# Power.net
KiCad netlist of a schematic drawn in Altium Designer
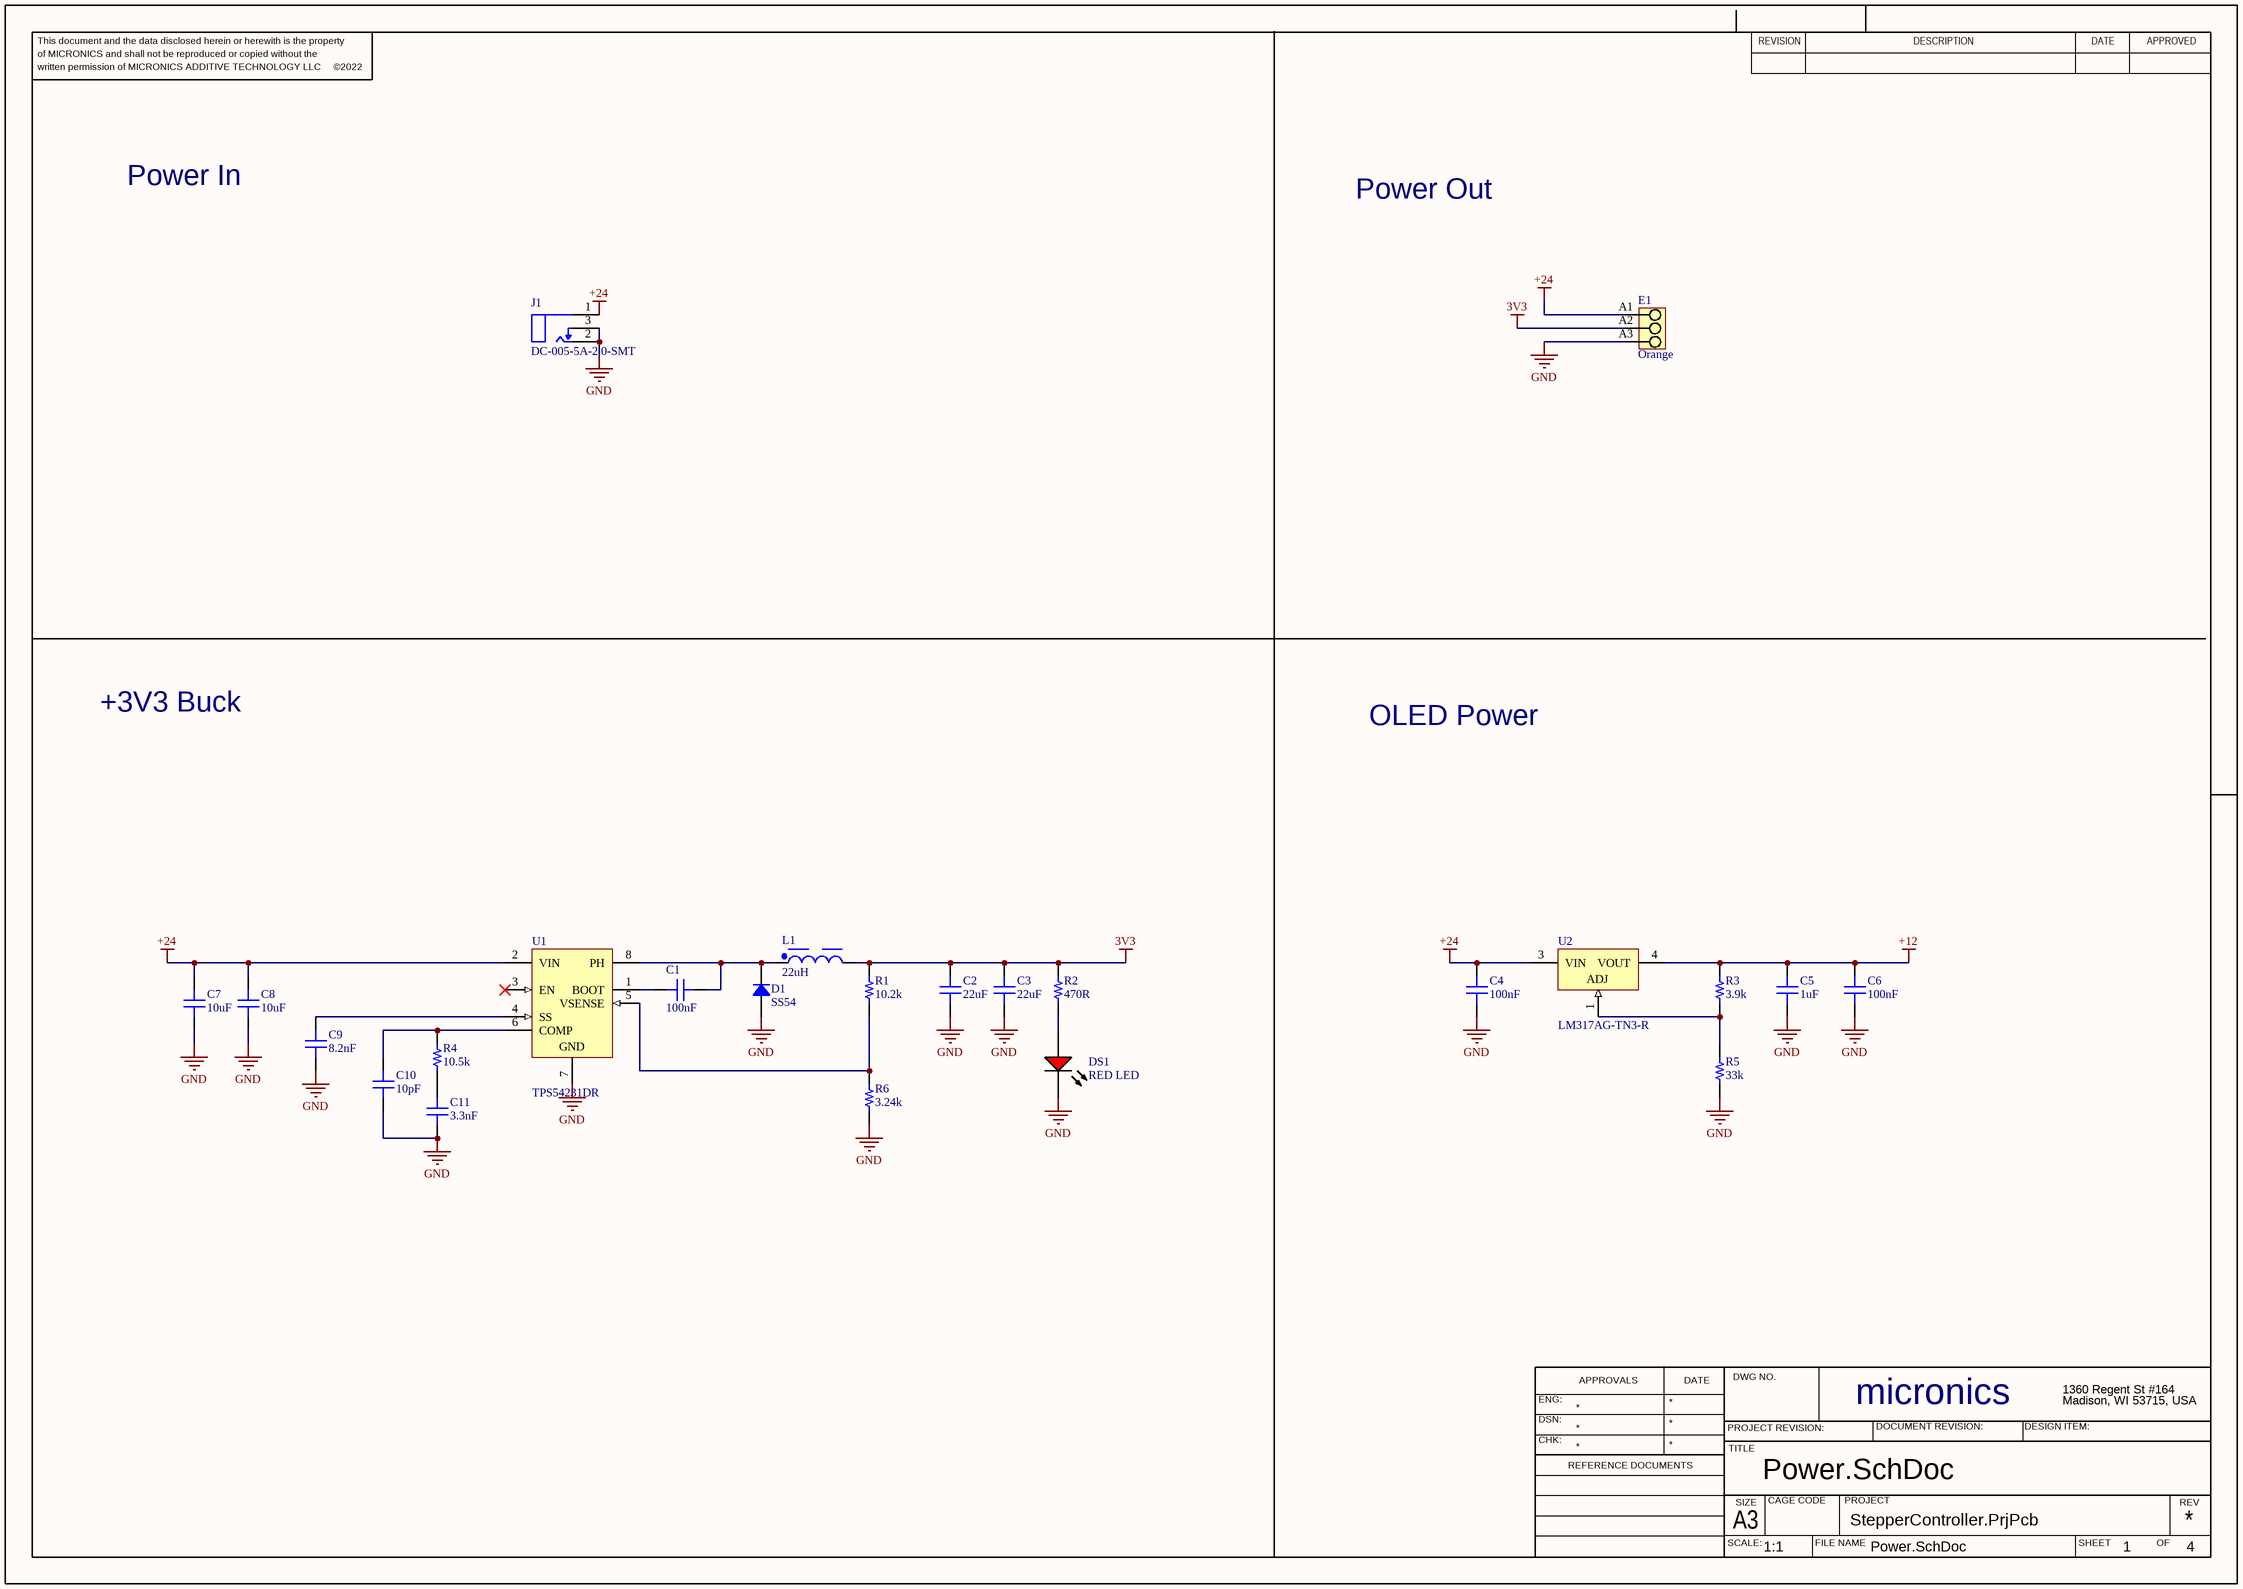
[diagram p0: Power.SchDoc]

(export (version "E")
  (design (tool "Eeschema 10.0.6"))
  (components
    (comp (ref "C1")
      (value "100nF")
      (footprint "CAP 0603_1608")
      (description "C14663")
      (fields
        (field (name "PART NUMBER") "250X14W223MV4T")
        (field (name "MANUFACTURER") "Johanson Dielectrics Inc.")
      )
      (libsource (lib "Celestial Altium Library - altium_library") (part "Capacitor"))
    )
    (comp (ref "C2")
      (value "22uF")
      (footprint "CAP 1206_3216 - 0.8MM")
      (description "C12891")
      (fields (field (name "PART NUMBER") "MM061A101JCT2A") (field (name "MANUFACTURER") "AVX Corporation"))
      (libsource (lib "Celestial Altium Library - altium_library") (part "Capacitor"))
    )
    (comp (ref "C3")
      (value "22uF")
      (footprint "CAP 1206_3216 - 0.8MM")
      (description "C12891")
      (fields (field (name "PART NUMBER") "MM061A101JCT2A") (field (name "MANUFACTURER") "AVX Corporation"))
      (libsource (lib "Celestial Altium Library - altium_library") (part "Capacitor"))
    )
    (comp (ref "C4")
      (value "100nF")
      (footprint "CAP 0603_1608")
      (description "CAP CER 0.022UF 25V X7R 0603")
      (fields
        (field (name "PART NUMBER") "250X14W223MV4T")
        (field (name "MANUFACTURER") "Johanson Dielectrics Inc.")
      )
      (libsource (lib "Celestial Altium Library - altium_library") (part "Capacitor"))
    )
    (comp (ref "C5")
      (value "1uF")
      (footprint "CAP 0603_1608")
      (description "CAP CER 0.022UF 25V X7R 0603")
      (fields
        (field (name "PART NUMBER") "250X14W223MV4T")
        (field (name "MANUFACTURER") "Johanson Dielectrics Inc.")
      )
      (libsource (lib "Celestial Altium Library - altium_library") (part "Capacitor"))
    )
    (comp (ref "C6")
      (value "100nF")
      (footprint "CAP 0603_1608")
      (description "CAP CER 0.022UF 25V X7R 0603")
      (fields
        (field (name "PART NUMBER") "250X14W223MV4T")
        (field (name "MANUFACTURER") "Johanson Dielectrics Inc.")
      )
      (libsource (lib "Celestial Altium Library - altium_library") (part "Capacitor"))
    )
    (comp (ref "C7")
      (value "10uF")
      (footprint "CAP 1206_3216 - 0.8MM")
      (description "C13585")
      (fields (field (name "PART NUMBER") "MM061A101JCT2A") (field (name "MANUFACTURER") "AVX Corporation"))
      (libsource (lib "Celestial Altium Library - altium_library") (part "Capacitor"))
    )
    (comp (ref "C8")
      (value "10uF")
      (footprint "CAP 1206_3216 - 0.8MM")
      (description "C13585")
      (fields (field (name "PART NUMBER") "MM061A101JCT2A") (field (name "MANUFACTURER") "AVX Corporation"))
      (libsource (lib "Celestial Altium Library - altium_library") (part "Capacitor"))
    )
    (comp (ref "C9")
      (value "8.2nF")
      (footprint "CAP 0603_1608")
      (fields
        (field (name "PART NUMBER") "250X14W223MV4T")
        (field (name "MANUFACTURER") "Johanson Dielectrics Inc.")
        (field (name "TOLERANCE") "±20%")
      )
      (libsource (lib "Celestial Altium Library - altium_library") (part "Capacitor"))
    )
    (comp (ref "C10")
      (value "10pF")
      (footprint "CAP 0603_1608")
      (fields
        (field (name "PART NUMBER") "250X14W223MV4T")
        (field (name "MANUFACTURER") "Johanson Dielectrics Inc.")
        (field (name "TOLERANCE") "±20%")
      )
      (libsource (lib "Celestial Altium Library - altium_library") (part "Capacitor"))
    )
    (comp (ref "C11")
      (value "3.3nF")
      (footprint "CAP 0603_1608")
      (fields
        (field (name "PART NUMBER") "250X14W223MV4T")
        (field (name "MANUFACTURER") "Johanson Dielectrics Inc.")
        (field (name "TOLERANCE") "±20%")
      )
      (libsource (lib "Celestial Altium Library - altium_library") (part "Capacitor"))
    )
    (comp (ref "D1")
      (value "SS54")
      (footprint "DO214AC SMA")
      (fields (field (name "MANUFACTURER") "ON Semiconductor"))
      (libsource (lib "Celestial Altium Library - altium_library") (part "Diode"))
    )
    (comp (ref "DS1")
      (value "RED LED")
      (footprint "VISH-TLMS1000_V")
      (description "0603 LED")
      (fields (field (name "MANUFACTURER") "Vishay"))
      (libsource (lib "Altium Content Vault") (part "LED-RED-AK-2"))
    )
    (comp (ref "E1")
      (value "Orange")
      (footprint "PM_5_08_90_03")
      (description "C430604")
      (fields (field (name "PARTNUMBER") "1760500000") (field (name "MANUFACTURER") "Weidmueller"))
      (libsource (lib "Altium Content Vault") (part "Terminal_03_1x03"))
    )
    (comp (ref "J1")
      (value "DC-005-5A-2.0-SMT")
      (footprint "FP-PJ-002BH-SMT-TR-MFG")
      (description "C319134")
      (fields
        (field (name "MANUFACTURER") "CUI Inc")
        (field (name "OCTOPART") "https://octopart.com/pj-002bh-smt-tr-cui-25947151")
      )
      (libsource (lib "Altium Content Vault") (part "020ff674638626da6de6501228ee46e"))
    )
    (comp (ref "L1")
      (value "22uH")
      (footprint "WE-PD_1050P")
      (description "C2651173")
      (fields (field (name "TOLERANCE") "20%"))
      (libsource (lib "Altium Content Vault") (part "Inductor - 2"))
    )
    (comp (ref "R1")
      (value "10.2k")
      (footprint "RES 0603_1608")
      (description "RES 23.2K OHM 0.5% 1/10W 0603")
      (fields
        (field (name "PART NUMBER") "RNCF0603DTE23K2")
        (field (name "MANUFACTURER") "Stackpole Electronics Inc")
      )
      (libsource (lib "Celestial Altium Library - altium_library") (part "Resistor"))
    )
    (comp (ref "R2")
      (value "470R")
      (footprint "RES 0603_1608")
      (description "RES 23.2K OHM 0.5% 1/10W 0603")
      (fields
        (field (name "PART NUMBER") "RNCF0603DTE23K2")
        (field (name "MANUFACTURER") "Stackpole Electronics Inc")
      )
      (libsource (lib "Celestial Altium Library - altium_library") (part "Resistor"))
    )
    (comp (ref "R3")
      (value "3.9k")
      (footprint "RES 0603_1608")
      (description "RES 23.2K OHM 0.5% 1/10W 0603")
      (fields
        (field (name "PART NUMBER") "RNCF0603DTE23K2")
        (field (name "MANUFACTURER") "Stackpole Electronics Inc")
      )
      (libsource (lib "Celestial Altium Library - altium_library") (part "Resistor"))
    )
    (comp (ref "R4")
      (value "10.5k")
      (footprint "RES 0603_1608")
      (description "RES 23.2K OHM 0.5% 1/10W 0603")
      (fields
        (field (name "PART NUMBER") "RNCF0603DTE23K2")
        (field (name "MANUFACTURER") "Stackpole Electronics Inc")
      )
      (libsource (lib "Celestial Altium Library - altium_library") (part "Resistor"))
    )
    (comp (ref "R5")
      (value "33k")
      (footprint "RES 0603_1608")
      (description "RES 23.2K OHM 0.5% 1/10W 0603")
      (fields
        (field (name "PART NUMBER") "RNCF0603DTE23K2")
        (field (name "MANUFACTURER") "Stackpole Electronics Inc")
      )
      (libsource (lib "Celestial Altium Library - altium_library") (part "Resistor"))
    )
    (comp (ref "R6")
      (value "3.24k")
      (footprint "RES 0603_1608")
      (description "RES 23.2K OHM 0.5% 1/10W 0603")
      (fields
        (field (name "PART NUMBER") "RNCF0603DTE23K2")
        (field (name "MANUFACTURER") "Stackpole Electronics Inc")
      )
      (libsource (lib "Celestial Altium Library - altium_library") (part "Resistor"))
    )
    (comp (ref "U1")
      (value "TPS54231DR")
      (footprint "D0008A_L")
      (fields (field (name "MANUFACTURER") "Texas Instruments"))
      (libsource (lib "Altium Content Vault") (part "TI-TPS54231D8"))
    )
    (comp (ref "U2")
      (value "LM317AG-TN3-R")
      (footprint "TO-252_L")
      (description "C75510")
      (libsource (lib "Altium Content Vault") (part "PM-REG-LM217M-SOT3"))
    )
  )
  (nets
    (net (code "1") (name "+12") (class "Default")
      (node (ref "C5") (pin "1") (pinfunction "1_1") (pintype "passive"))
      (node (ref "C6") (pin "1") (pinfunction "1_1") (pintype "passive"))
      (node (ref "R3") (pin "2") (pinfunction "2_2") (pintype "passive"))
      (node (ref "U2") (pin "4") (pinfunction "VOUT_4") (pintype "power_in"))
    )
    (net (code "2") (name "+24") (class "Default")
      (node (ref "C4") (pin "1") (pinfunction "1_1") (pintype "passive"))
      (node (ref "C7") (pin "2") (pinfunction "2_2") (pintype "passive"))
      (node (ref "C8") (pin "2") (pinfunction "2_2") (pintype "passive"))
      (node (ref "E1") (pin "A1") (pinfunction "A1_A1") (pintype "passive"))
      (node (ref "J1") (pin "1") (pinfunction "1_1") (pintype "passive"))
      (node (ref "U1") (pin "2") (pinfunction "VIN_2") (pintype "power_in"))
      (node (ref "U2") (pin "3") (pinfunction "VIN_3") (pintype "power_in"))
    )
    (net (code "3") (name "3V3") (class "Default")
      (node (ref "C2") (pin "2") (pinfunction "2_2") (pintype "passive"))
      (node (ref "C3") (pin "2") (pinfunction "2_2") (pintype "passive"))
      (node (ref "E1") (pin "A2") (pinfunction "A2_A2") (pintype "passive"))
      (node (ref "L1") (pin "2") (pinfunction "2_2") (pintype "passive"))
      (node (ref "R1") (pin "2") (pinfunction "2_2") (pintype "passive"))
      (node (ref "R2") (pin "2") (pinfunction "2_2") (pintype "passive"))
    )
    (net (code "4") (name "GND") (class "Default")
      (node (ref "C10") (pin "1") (pinfunction "1_1") (pintype "passive"))
      (node (ref "C11") (pin "1") (pinfunction "1_1") (pintype "passive"))
      (node (ref "C2") (pin "1") (pinfunction "1_1") (pintype "passive"))
      (node (ref "C3") (pin "1") (pinfunction "1_1") (pintype "passive"))
      (node (ref "C4") (pin "2") (pinfunction "2_2") (pintype "passive"))
      (node (ref "C5") (pin "2") (pinfunction "2_2") (pintype "passive"))
      (node (ref "C6") (pin "2") (pinfunction "2_2") (pintype "passive"))
      (node (ref "C7") (pin "1") (pinfunction "1_1") (pintype "passive"))
      (node (ref "C8") (pin "1") (pinfunction "1_1") (pintype "passive"))
      (node (ref "C9") (pin "1") (pinfunction "1_1") (pintype "passive"))
      (node (ref "D1") (pin "1") (pinfunction "1_1") (pintype "passive"))
      (node (ref "DS1") (pin "2") (pinfunction "K_2") (pintype "passive"))
      (node (ref "E1") (pin "A3") (pinfunction "A3_A3") (pintype "passive"))
      (node (ref "J1") (pin "2") (pinfunction "2_2") (pintype "passive"))
      (node (ref "J1") (pin "3") (pinfunction "3_3") (pintype "passive"))
      (node (ref "R5") (pin "1") (pinfunction "1_1") (pintype "passive"))
      (node (ref "R6") (pin "1") (pinfunction "1_1") (pintype "passive"))
      (node (ref "U1") (pin "7") (pinfunction "GND_7") (pintype "power_in"))
    )
    (net (code "5") (name "Net-(C11-Pad2)") (class "Default")
      (node (ref "C11") (pin "2") (pinfunction "2_2") (pintype "passive"))
      (node (ref "R4") (pin "1") (pinfunction "1_1") (pintype "passive"))
    )
    (net (code "6") (name "Net-(DS1-A)") (class "Default")
      (node (ref "DS1") (pin "1") (pinfunction "A_1") (pintype "passive"))
      (node (ref "R2") (pin "1") (pinfunction "1_1") (pintype "passive"))
    )
    (net (code "7") (name "Net-(U1-BOOT)") (class "Default")
      (node (ref "C1") (pin "2") (pinfunction "2_2") (pintype "passive"))
      (node (ref "U1") (pin "1") (pinfunction "BOOT_1") (pintype "passive"))
    )
    (net (code "8") (name "Net-(U1-COMP)") (class "Default")
      (node (ref "C10") (pin "2") (pinfunction "2_2") (pintype "passive"))
      (node (ref "R4") (pin "2") (pinfunction "2_2") (pintype "passive"))
      (node (ref "U1") (pin "6") (pinfunction "COMP_6") (pintype "passive"))
    )
    (net (code "9") (name "Net-(U1-PH)") (class "Default")
      (node (ref "C1") (pin "1") (pinfunction "1_1") (pintype "passive"))
      (node (ref "D1") (pin "2") (pinfunction "2_2") (pintype "passive"))
      (node (ref "L1") (pin "1") (pinfunction "1_1") (pintype "passive"))
      (node (ref "U1") (pin "8") (pinfunction "PH_8") (pintype "power_in"))
    )
    (net (code "10") (name "Net-(U1-SS)") (class "Default")
      (node (ref "C9") (pin "2") (pinfunction "2_2") (pintype "passive"))
      (node (ref "U1") (pin "4") (pinfunction "SS_4") (pintype "input"))
    )
    (net (code "11") (name "Net-(U1-VSENSE)") (class "Default")
      (node (ref "R1") (pin "1") (pinfunction "1_1") (pintype "passive"))
      (node (ref "R6") (pin "2") (pinfunction "2_2") (pintype "passive"))
      (node (ref "U1") (pin "5") (pinfunction "VSENSE_5") (pintype "input"))
    )
    (net (code "12") (name "Net-(U2-ADJ)") (class "Default")
      (node (ref "R3") (pin "1") (pinfunction "1_1") (pintype "passive"))
      (node (ref "R5") (pin "2") (pinfunction "2_2") (pintype "passive"))
      (node (ref "U2") (pin "1") (pinfunction "ADJ_1") (pintype "input"))
    )
    (net (code "13") (name "unconnected-(U1-EN-Pad3)") (class "Default")
      (node (ref "U1") (pin "3") (pinfunction "EN_3") (pintype "input+no_connect"))
    )
  )
)
